# Fri3D_IRA_Power.net
KiCad netlist of a schematic drawn in Altium Designer
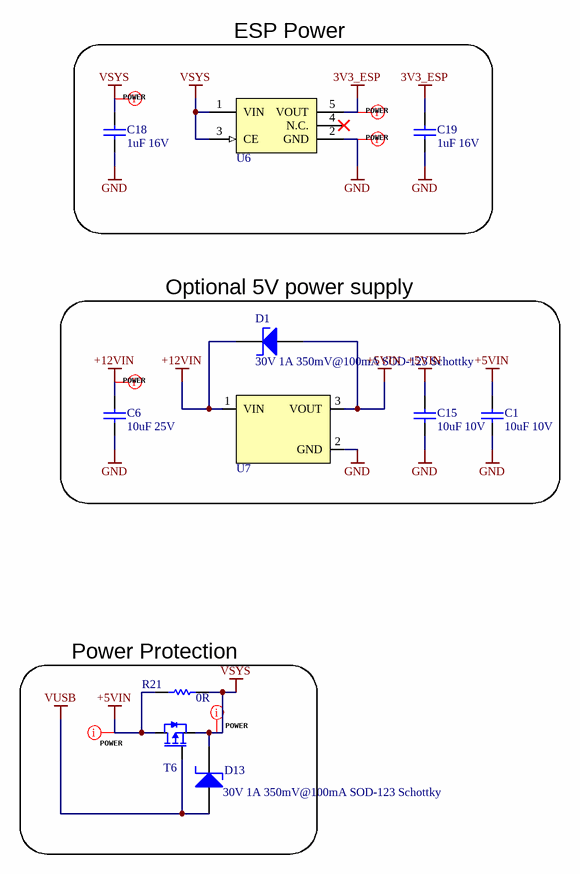
[diagram p0: Fri3D_IRA_Power.SchDoc]

(export (version "E")
  (design (tool "Eeschema 10.0.6"))
  (components
    (comp (ref "C1")
      (value "10uF 10V")
      (footprint "C0805_N")
      (description "CAP # 10uF 10V 0805")
      (fields (field (name "Comment") "CAP_CERAMIC"))
      (libsource (lib "Phyx_Components") (part "CAP_CERAMIC"))
    )
    (comp (ref "C6")
      (value "10uF 25V")
      (footprint "C0805_N")
      (description "Capacitor Ceramic")
      (libsource (lib "Phyx_Components") (part "CAP_CERAMIC"))
    )
    (comp (ref "C15")
      (value "10uF 10V")
      (footprint "C0805_N")
      (description "CAP # 10uF 10V 0805")
      (fields (field (name "Comment") "CAP_CERAMIC"))
      (libsource (lib "Phyx_Components") (part "CAP_CERAMIC"))
    )
    (comp (ref "C18")
      (value "1uF 16V")
      (footprint "C0603_N")
      (description "Capacitor Ceramic")
      (libsource (lib "Phyx_Components") (part "CAP_CERAMIC"))
    )
    (comp (ref "C19")
      (value "1uF 16V")
      (footprint "C0603_N")
      (description "Capacitor Ceramic")
      (libsource (lib "Phyx_Components") (part "CAP_CERAMIC"))
    )
    (comp (ref "D1")
      (value "30V 1A 350mV@100mA SOD-123 Schottky")
      (footprint "ON_SOD-123FL_AC")
      (description "Schottky # LMBR130T1G")
      (libsource (lib "Phyx_Components") (part "Schottky_AC"))
    )
    (comp (ref "D13")
      (value "30V 1A 350mV@100mA SOD-123 Schottky")
      (footprint "ON_SOD-123FL_AC")
      (description "Schottky # LMBR130T1G")
      (libsource (lib "Phyx_Components") (part "Schottky_AC"))
    )
    (comp (ref "R21")
      (value "0R")
      (footprint "R0603_N")
      (libsource (lib "Phyx_Components") (part "RESISTOR"))
    )
    (comp (ref "T6")
      (value "-2.3A -20V P-Ch MOSFET Vgs -1V")
      (footprint "SOT23-3")
      (description "=Description")
      (libsource (lib "Phyx_Components") (part "P_MOSFET_GSD"))
    )
    (comp (ref "U6")
      (value "3V3 LDO 700mA 50mV")
      (footprint "SOT23-5")
      (description "=Designator")
      (libsource (lib "Phyx_Components") (part "XC6210_SOT"))
    )
    (comp (ref "U7")
      (value "Mornsun K7805-500R3-LB 5V 500mA 4.75~36Vin")
      (footprint "K78xx-500R3-LB")
      (description "=Designator")
      (libsource (lib "Phyx_Components") (part "LDO_78xx"))
    )
  )
  (nets
    (net (code "1") (name "+5VIN") (class "Default")
      (node (ref "C1") (pin "1") (pinfunction "1_1") (pintype "passive"))
      (node (ref "C15") (pin "1") (pinfunction "1_1") (pintype "passive"))
      (node (ref "D1") (pin "A") (pinfunction "A_A") (pintype "passive"))
      (node (ref "R21") (pin "2") (pinfunction "2_2") (pintype "passive"))
      (node (ref "T6") (pin "3") (pinfunction "D_3") (pintype "passive"))
      (node (ref "U7") (pin "3") (pinfunction "VOUT_3") (pintype "power_in"))
    )
    (net (code "2") (name "+12VIN") (class "Default")
      (node (ref "C6") (pin "1") (pinfunction "1_1") (pintype "passive"))
      (node (ref "D1") (pin "C") (pinfunction "C_C") (pintype "passive"))
      (node (ref "U7") (pin "1") (pinfunction "VIN_1") (pintype "power_in"))
    )
    (net (code "3") (name "3V3_ESP") (class "Default")
      (node (ref "C19") (pin "1") (pinfunction "1_1") (pintype "passive"))
      (node (ref "U6") (pin "5") (pinfunction "VOUT_5") (pintype "power_in"))
    )
    (net (code "4") (name "GND") (class "Default")
      (node (ref "C1") (pin "2") (pinfunction "2_2") (pintype "passive"))
      (node (ref "C15") (pin "2") (pinfunction "2_2") (pintype "passive"))
      (node (ref "C18") (pin "2") (pinfunction "2_2") (pintype "passive"))
      (node (ref "C19") (pin "2") (pinfunction "2_2") (pintype "passive"))
      (node (ref "C6") (pin "2") (pinfunction "2_2") (pintype "passive"))
      (node (ref "U6") (pin "2") (pinfunction "GND_2") (pintype "power_in"))
      (node (ref "U7") (pin "2") (pinfunction "GND_2") (pintype "power_in"))
    )
    (net (code "5") (name "VSYS") (class "Default")
      (node (ref "C18") (pin "1") (pinfunction "1_1") (pintype "passive"))
      (node (ref "D13") (pin "C") (pinfunction "C_C") (pintype "passive"))
      (node (ref "R21") (pin "1") (pinfunction "1_1") (pintype "passive"))
      (node (ref "T6") (pin "2") (pinfunction "S_2") (pintype "passive"))
      (node (ref "U6") (pin "1") (pinfunction "VIN_1") (pintype "power_in"))
      (node (ref "U6") (pin "3") (pinfunction "CE_3") (pintype "input"))
    )
    (net (code "6") (name "VUSB") (class "Default")
      (node (ref "D13") (pin "A") (pinfunction "A_A") (pintype "passive"))
      (node (ref "T6") (pin "1") (pinfunction "G_1") (pintype "passive"))
    )
    (net (code "7") (name "unconnected-(U6-N.C.-Pad4)") (class "Default")
      (node (ref "U6") (pin "4") (pinfunction "N.C._4") (pintype "passive+no_connect"))
    )
  )
)
